# 555_ckt.net
KiCad netlist of a schematic drawn in EAGLE
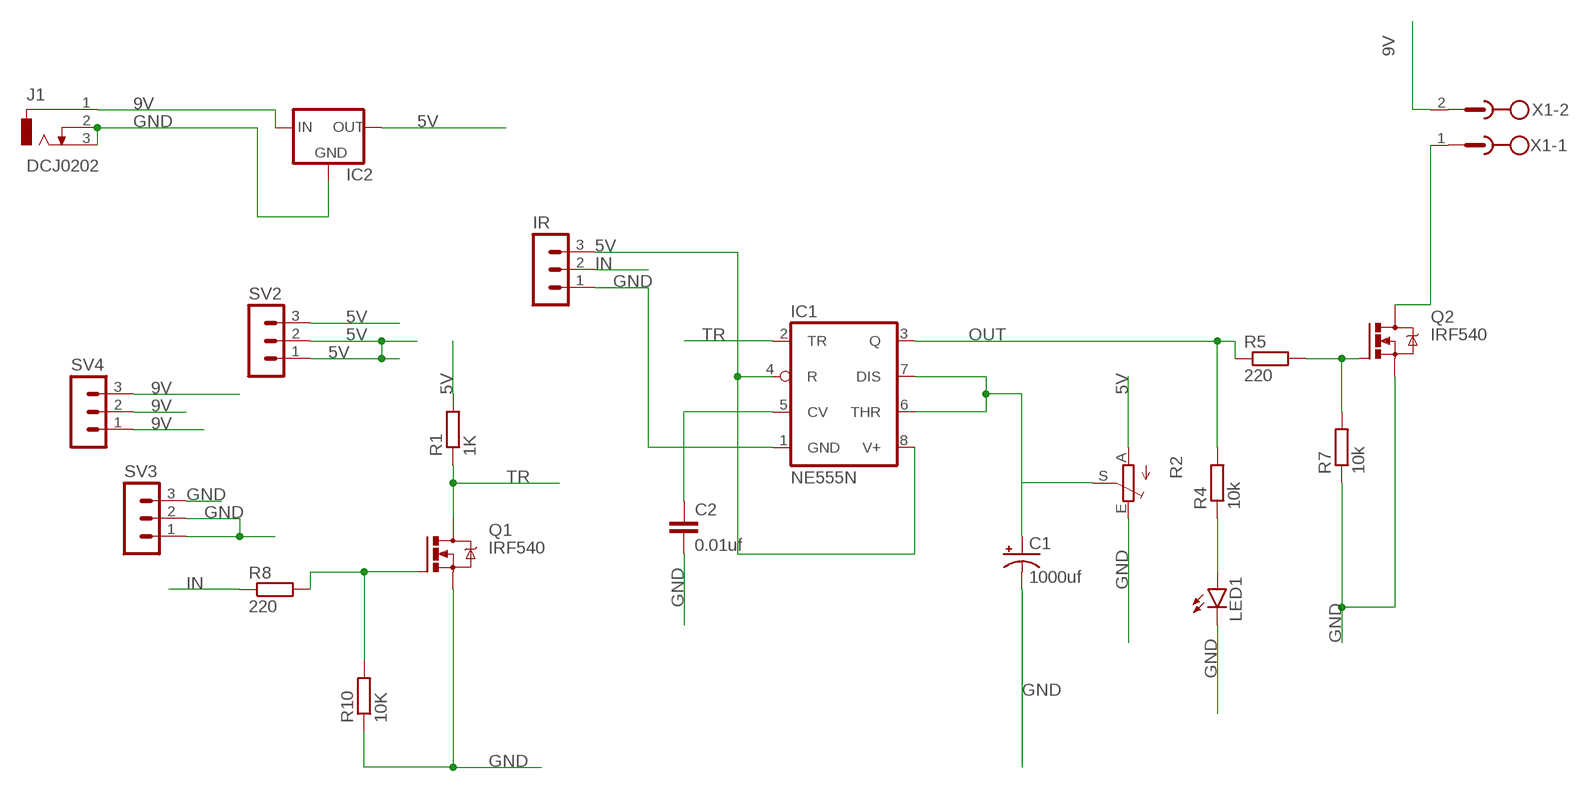
[diagram p0: schematic, sheet 1]

(export (version "E")
  (design (tool "Eeschema 10.0.6"))
  (components
    (comp (ref "C1")
      (value "1000uf")
      (footprint "eagle-import:E2,5-7")
      (libsource (lib "eagle-import") (part "CPOL-USE2.5-7"))
    )
    (comp (ref "C2")
      (value "0.01uf")
      (footprint "eagle-import:C025-024X044")
      (libsource (lib "eagle-import") (part "C-EU025-024X044"))
    )
    (comp (ref "IC1")
      (value "NE555N")
      (footprint "eagle-import:DIL08")
      (libsource (lib "eagle-import") (part "555NNE"))
    )
    (comp (ref "IC2")
      (value "78XXL")
      (footprint "eagle-import:78XXL")
      (libsource (lib "eagle-import") (part "78XXL"))
    )
    (comp (ref "IR")
      (value "MA03-1")
      (footprint "eagle-import:MA03-1")
      (libsource (lib "eagle-import") (part "MA03-1"))
    )
    (comp (ref "J1")
      (value "DCJ0202")
      (footprint "eagle-import:DCJ0202")
      (libsource (lib "eagle-import") (part "DCJ0202"))
    )
    (comp (ref "LED1")
      (value "LED3MM")
      (footprint "eagle-import:LED3MM")
      (libsource (lib "eagle-import") (part "LED3MM"))
    )
    (comp (ref "Q1")
      (value "IRF540")
      (footprint "eagle-import:TO220BV")
      (libsource (lib "eagle-import") (part "IRF540"))
    )
    (comp (ref "Q2")
      (value "IRF540")
      (footprint "eagle-import:TO220BV")
      (libsource (lib "eagle-import") (part "IRF540"))
    )
    (comp (ref "R1")
      (value "1K")
      (footprint "eagle-import:0207_10")
      (libsource (lib "eagle-import") (part "R-EU_0207/10"))
    )
    (comp (ref "R2")
      (value "TRIM_EU-B64Y")
      (footprint "eagle-import:B64Y")
      (libsource (lib "eagle-import") (part "TRIM_EU-B64Y"))
    )
    (comp (ref "R4")
      (value "10k")
      (footprint "eagle-import:0207_10")
      (libsource (lib "eagle-import") (part "R-EU_0207/10"))
    )
    (comp (ref "R5")
      (value "220")
      (footprint "eagle-import:0207_10")
      (libsource (lib "eagle-import") (part "R-EU_0207/10"))
    )
    (comp (ref "R7")
      (value "10k")
      (footprint "eagle-import:0207_10")
      (libsource (lib "eagle-import") (part "R-EU_0207/10"))
    )
    (comp (ref "R8")
      (value "220")
      (footprint "eagle-import:0207_10")
      (libsource (lib "eagle-import") (part "R-EU_0207/10"))
    )
    (comp (ref "R10")
      (value "10K")
      (footprint "eagle-import:0207_10")
      (libsource (lib "eagle-import") (part "R-EU_0207/10"))
    )
    (comp (ref "SV2")
      (value "MA03-1")
      (footprint "eagle-import:MA03-1")
      (libsource (lib "eagle-import") (part "MA03-1"))
    )
    (comp (ref "SV3")
      (value "MA03-1")
      (footprint "eagle-import:MA03-1")
      (libsource (lib "eagle-import") (part "MA03-1"))
    )
    (comp (ref "SV4")
      (value "MA03-1")
      (footprint "eagle-import:MA03-1")
      (libsource (lib "eagle-import") (part "MA03-1"))
    )
    (comp (ref "X1")
      (value "MSTBV2")
      (footprint "eagle-import:MSTBV2")
      (libsource (lib "eagle-import") (part "MSTBV2"))
    )
  )
  (nets
    (net (code "1") (name "/5V") (class "Default")
      (node (ref "IC1") (pin "4") (pinfunction "R_4") (pintype "input"))
      (node (ref "IC1") (pin "8") (pinfunction "V+_8") (pintype "power_in"))
      (node (ref "IC2") (pin "OUT") (pinfunction "OUT_OUT") (pintype "passive"))
      (node (ref "IR") (pin "3") (pinfunction "3_3") (pintype "passive"))
      (node (ref "R1") (pin "2") (pinfunction "2_2") (pintype "passive"))
      (node (ref "R2") (pin "A") (pinfunction "A_A") (pintype "passive"))
      (node (ref "SV2") (pin "1") (pinfunction "1_1") (pintype "passive"))
      (node (ref "SV2") (pin "2") (pinfunction "2_2") (pintype "passive"))
      (node (ref "SV2") (pin "3") (pinfunction "3_3") (pintype "passive"))
    )
    (net (code "2") (name "/9V") (class "Default")
      (node (ref "IC2") (pin "IN") (pinfunction "IN_IN") (pintype "input"))
      (node (ref "J1") (pin "1") (pinfunction "1_1") (pintype "passive"))
      (node (ref "SV4") (pin "1") (pinfunction "1_1") (pintype "passive"))
      (node (ref "SV4") (pin "2") (pinfunction "2_2") (pintype "passive"))
      (node (ref "SV4") (pin "3") (pinfunction "3_3") (pintype "passive"))
      (node (ref "X1") (pin "2") (pinfunction "SK_2") (pintype "passive"))
    )
    (net (code "3") (name "/GND") (class "Default")
      (node (ref "C1") (pin "-") (pinfunction "-_-") (pintype "passive"))
      (node (ref "C2") (pin "2") (pinfunction "2_2") (pintype "passive"))
      (node (ref "IC1") (pin "1") (pinfunction "GND_1") (pintype "power_in"))
      (node (ref "IC2") (pin "GND") (pinfunction "GND_GND") (pintype "input"))
      (node (ref "IR") (pin "1") (pinfunction "1_1") (pintype "passive"))
      (node (ref "J1") (pin "2") (pinfunction "2_2") (pintype "passive"))
      (node (ref "J1") (pin "3") (pinfunction "3_3") (pintype "passive"))
      (node (ref "LED1") (pin "K") (pinfunction "C_K") (pintype "passive"))
      (node (ref "Q1") (pin "S") (pinfunction "S_S") (pintype "passive"))
      (node (ref "Q2") (pin "S") (pinfunction "S_S") (pintype "passive"))
      (node (ref "R10") (pin "1") (pinfunction "1_1") (pintype "passive"))
      (node (ref "R2") (pin "E") (pinfunction "E_E") (pintype "passive"))
      (node (ref "R7") (pin "1") (pinfunction "1_1") (pintype "passive"))
      (node (ref "SV3") (pin "1") (pinfunction "1_1") (pintype "passive"))
      (node (ref "SV3") (pin "2") (pinfunction "2_2") (pintype "passive"))
      (node (ref "SV3") (pin "3") (pinfunction "3_3") (pintype "passive"))
    )
    (net (code "4") (name "/IN") (class "Default")
      (node (ref "IR") (pin "2") (pinfunction "2_2") (pintype "passive"))
      (node (ref "R8") (pin "1") (pinfunction "1_1") (pintype "passive"))
    )
    (net (code "5") (name "/OUT") (class "Default")
      (node (ref "IC1") (pin "3") (pinfunction "Q_3") (pintype "output"))
      (node (ref "R4") (pin "2") (pinfunction "2_2") (pintype "passive"))
      (node (ref "R5") (pin "1") (pinfunction "1_1") (pintype "passive"))
    )
    (net (code "6") (name "/TR") (class "Default")
      (node (ref "IC1") (pin "2") (pinfunction "TR_2") (pintype "input"))
      (node (ref "Q1") (pin "D") (pinfunction "D_D") (pintype "passive"))
      (node (ref "R1") (pin "1") (pinfunction "1_1") (pintype "passive"))
    )
    (net (code "7") (name "Net-(IC1-CV)") (class "Default")
      (node (ref "C2") (pin "1") (pinfunction "1_1") (pintype "passive"))
      (node (ref "IC1") (pin "5") (pinfunction "CV_5") (pintype "input"))
    )
    (net (code "8") (name "Net-(IC1-DIS)") (class "Default")
      (node (ref "C1") (pin "+") (pinfunction "+_+") (pintype "passive"))
      (node (ref "IC1") (pin "6") (pinfunction "THR_6") (pintype "input"))
      (node (ref "IC1") (pin "7") (pinfunction "DIS_7") (pintype "input"))
      (node (ref "R2") (pin "S") (pinfunction "S_S") (pintype "passive"))
    )
    (net (code "9") (name "Net-(LED1-PadA)") (class "Default")
      (node (ref "LED1") (pin "A") (pinfunction "A_A") (pintype "passive"))
      (node (ref "R4") (pin "1") (pinfunction "1_1") (pintype "passive"))
    )
    (net (code "10") (name "Net-(Q1-PadG)") (class "Default")
      (node (ref "Q1") (pin "G") (pinfunction "G_G") (pintype "passive"))
      (node (ref "R10") (pin "2") (pinfunction "2_2") (pintype "passive"))
      (node (ref "R8") (pin "2") (pinfunction "2_2") (pintype "passive"))
    )
    (net (code "11") (name "Net-(Q2-PadG)") (class "Default")
      (node (ref "Q2") (pin "G") (pinfunction "G_G") (pintype "passive"))
      (node (ref "R5") (pin "2") (pinfunction "2_2") (pintype "passive"))
      (node (ref "R7") (pin "2") (pinfunction "2_2") (pintype "passive"))
    )
    (net (code "12") (name "Net-(X1A-SK)") (class "Default")
      (node (ref "Q2") (pin "D") (pinfunction "D_D") (pintype "passive"))
      (node (ref "X1") (pin "1") (pinfunction "SK_1") (pintype "passive"))
    )
  )
)
